# Direction.net
KiCad netlist of a schematic drawn in Altium Designer
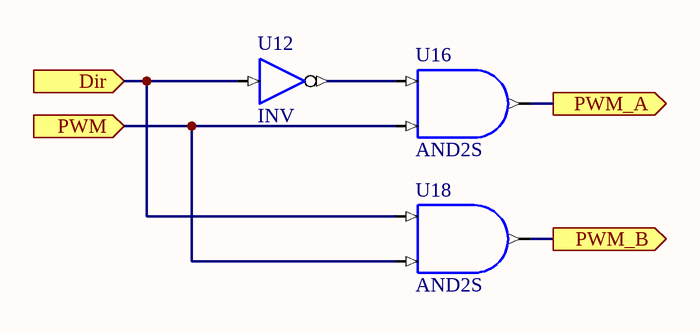
[diagram p0: Direction.SchDoc]

(export (version "E")
  (design (tool "Eeschema 10.0.6"))
  (components
    (comp (ref "U12")
      (value "INV")
      (description "Inverter")
      (fields (field (name "PUBLISHER") "Altium Limited"))
      (libsource (lib "FPGA Generic") (part "INV"))
    )
    (comp (ref "U16")
      (value "AND2S")
      (description "2-Input AND Gate, Single Pin Version")
      (fields (field (name "PUBLISHER") "Altium Limited"))
      (libsource (lib "FPGA Generic") (part "AND2S"))
    )
    (comp (ref "U18")
      (value "AND2S")
      (description "2-Input AND Gate, Single Pin Version")
      (fields (field (name "PUBLISHER") "Altium Limited"))
      (libsource (lib "FPGA Generic") (part "AND2S"))
    )
  )
  (nets
    (net (code "1") (name "/Dir") (class "Default")
      (node (ref "U12") (pin "I") (pinfunction "I_I") (pintype "input"))
      (node (ref "U18") (pin "I0") (pinfunction "I0_I0") (pintype "input"))
    )
    (net (code "2") (name "/PWM") (class "Default")
      (node (ref "U16") (pin "I1") (pinfunction "I1_I1") (pintype "input"))
      (node (ref "U18") (pin "I1") (pinfunction "I1_I1") (pintype "input"))
    )
    (net (code "3") (name "/PWM_A") (class "Default")
      (node (ref "U16") (pin "O") (pinfunction "O_O") (pintype "output"))
    )
    (net (code "4") (name "/PWM_B") (class "Default")
      (node (ref "U18") (pin "O") (pinfunction "O_O") (pintype "output"))
    )
    (net (code "5") (name "Net-(U12-PadO)") (class "Default")
      (node (ref "U12") (pin "O") (pinfunction "O_O") (pintype "output"))
      (node (ref "U16") (pin "I0") (pinfunction "I0_I0") (pintype "input"))
    )
  )
)
